# motherboard.net
KiCad netlist of a schematic drawn in EAGLE
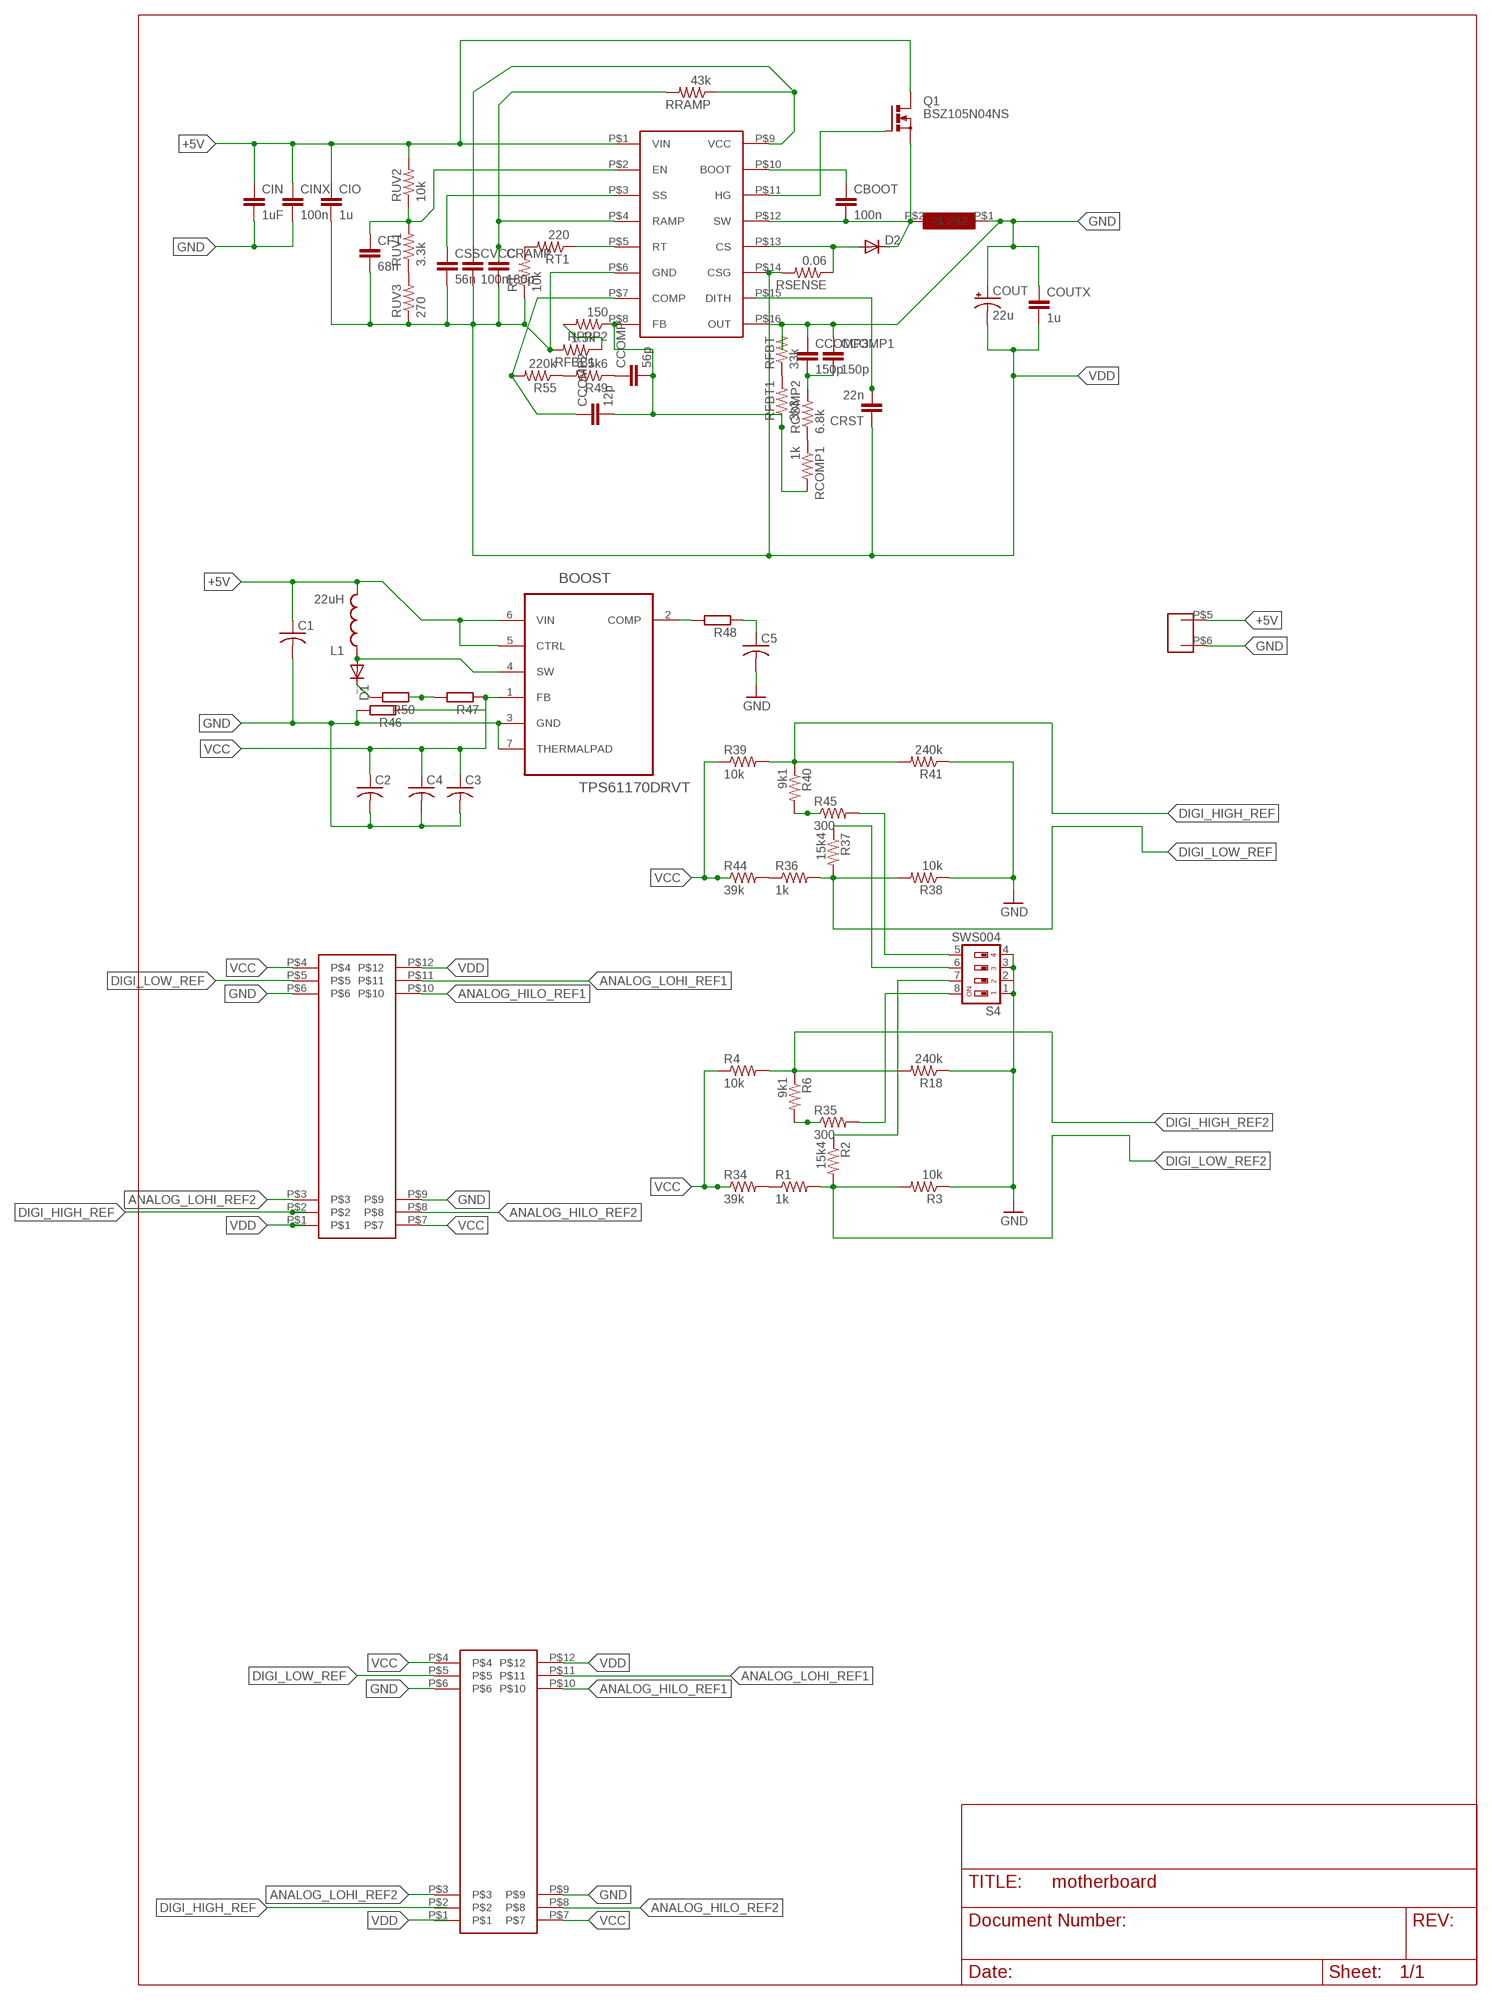
[diagram p0: schematic, sheet 1]

(export (version "E")
  (design (tool "Eeschema 10.0.6"))
  (components
    (comp (ref "BOOST")
      (value "TPS61170DRVT")
      (footprint "eagle-import:SON65P210X210X80-7N")
      (libsource (lib "eagle-import") (part "TPS61170DRVT"))
    )
    (comp (ref "C1")
      (value "C-USC1206")
      (footprint "eagle-import:C1206")
      (libsource (lib "eagle-import") (part "C-USC1206"))
    )
    (comp (ref "C2")
      (value "C-USC0805")
      (footprint "eagle-import:C0805")
      (libsource (lib "eagle-import") (part "C-USC0805"))
    )
    (comp (ref "C3")
      (value "C-USC1206")
      (footprint "eagle-import:C1206")
      (libsource (lib "eagle-import") (part "C-USC1206"))
    )
    (comp (ref "C4")
      (value "C-USC1206")
      (footprint "eagle-import:C1206")
      (libsource (lib "eagle-import") (part "C-USC1206"))
    )
    (comp (ref "C5")
      (value "C-USC1206")
      (footprint "eagle-import:C1206")
      (libsource (lib "eagle-import") (part "C-USC1206"))
    )
    (comp (ref "CBOOT")
      (value "100n")
      (footprint "eagle-import:C0805")
      (libsource (lib "eagle-import") (part "C-EUC0805"))
    )
    (comp (ref "CCOMP")
      (value "56p")
      (footprint "eagle-import:C0805")
      (libsource (lib "eagle-import") (part "C-EUC0805"))
    )
    (comp (ref "CCOMP1")
      (value "150p")
      (footprint "eagle-import:C0805")
      (libsource (lib "eagle-import") (part "C-EUC0805"))
    )
    (comp (ref "CCOMP2")
      (value "12p")
      (footprint "eagle-import:C0805")
      (libsource (lib "eagle-import") (part "C-EUC0805"))
    )
    (comp (ref "CCOMP3")
      (value "150p")
      (footprint "eagle-import:C0805")
      (libsource (lib "eagle-import") (part "C-EUC0805"))
    )
    (comp (ref "CFT")
      (value "68n")
      (footprint "eagle-import:C0805")
      (libsource (lib "eagle-import") (part "C-EUC0805"))
    )
    (comp (ref "CIN")
      (value "1uF")
      (footprint "eagle-import:C0805")
      (libsource (lib "eagle-import") (part "C-EUC0805"))
    )
    (comp (ref "CINX")
      (value "100n")
      (footprint "eagle-import:C0805")
      (libsource (lib "eagle-import") (part "C-EUC0805"))
    )
    (comp (ref "CIO")
      (value "1u")
      (footprint "eagle-import:C0805")
      (libsource (lib "eagle-import") (part "C-EUC0805"))
    )
    (comp (ref "COUT")
      (value "22u")
      (footprint "eagle-import:E5-5")
      (libsource (lib "eagle-import") (part "CPOL-USE5-5"))
    )
    (comp (ref "COUTX")
      (value "1u")
      (footprint "eagle-import:C0805")
      (libsource (lib "eagle-import") (part "C-EUC0805"))
    )
    (comp (ref "CRAMP")
      (value "180p")
      (footprint "eagle-import:C0805")
      (libsource (lib "eagle-import") (part "C-EUC0805"))
    )
    (comp (ref "CRST")
      (value "22n")
      (footprint "eagle-import:C0805")
      (libsource (lib "eagle-import") (part "C-EUC0805"))
    )
    (comp (ref "CSS")
      (value "56n")
      (footprint "eagle-import:C0805")
      (libsource (lib "eagle-import") (part "C-EUC0805"))
    )
    (comp (ref "CVCC")
      (value "100n")
      (footprint "eagle-import:C0805")
      (libsource (lib "eagle-import") (part "C-EUC0805"))
    )
    (comp (ref "D1")
      (value "DIODE-SOD123")
      (footprint "eagle-import:SOD123")
      (libsource (lib "eagle-import") (part "DIODE-SOD123"))
    )
    (comp (ref "D2")
      (value "DIODE-SOD123")
      (footprint "eagle-import:SOD123")
      (libsource (lib "eagle-import") (part "DIODE-SOD123"))
    )
    (comp (ref "L1")
      (value "22uH")
      (footprint "eagle-import:SRN6045")
      (libsource (lib "eagle-import") (part "INDUCTORBOURNS_SRN6045"))
    )
    (comp (ref "Q1")
      (value "BSZ105N04NS")
      (footprint "eagle-import:PG-TDSON-8")
      (libsource (lib "eagle-import") (part "BSZ105N04NS"))
    )
    (comp (ref "R1")
      (value "1k")
      (footprint "eagle-import:R0805")
      (libsource (lib "eagle-import") (part "R-US_R0805"))
    )
    (comp (ref "R2")
      (value "15k4")
      (footprint "eagle-import:R0805")
      (libsource (lib "eagle-import") (part "R-US_R0805"))
    )
    (comp (ref "R3")
      (value "10k")
      (footprint "eagle-import:R0805")
      (libsource (lib "eagle-import") (part "R-US_R0805"))
    )
    (comp (ref "R4")
      (value "10k")
      (footprint "eagle-import:R0805")
      (libsource (lib "eagle-import") (part "R-US_R0805"))
    )
    (comp (ref "R6")
      (value "9k1")
      (footprint "eagle-import:R0805")
      (libsource (lib "eagle-import") (part "R-US_R0805"))
    )
    (comp (ref "R18")
      (value "240k")
      (footprint "eagle-import:R0805")
      (libsource (lib "eagle-import") (part "R-US_R0805"))
    )
    (comp (ref "R34")
      (value "39k")
      (footprint "eagle-import:R0805")
      (libsource (lib "eagle-import") (part "R-US_R0805"))
    )
    (comp (ref "R35")
      (value "300")
      (footprint "eagle-import:R0805")
      (libsource (lib "eagle-import") (part "R-US_R0805"))
    )
    (comp (ref "R36")
      (value "1k")
      (footprint "eagle-import:R0805")
      (libsource (lib "eagle-import") (part "R-US_R0805"))
    )
    (comp (ref "R37")
      (value "15k4")
      (footprint "eagle-import:R0805")
      (libsource (lib "eagle-import") (part "R-US_R0805"))
    )
    (comp (ref "R38")
      (value "10k")
      (footprint "eagle-import:R0805")
      (libsource (lib "eagle-import") (part "R-US_R0805"))
    )
    (comp (ref "R39")
      (value "10k")
      (footprint "eagle-import:R0805")
      (libsource (lib "eagle-import") (part "R-US_R0805"))
    )
    (comp (ref "R40")
      (value "9k1")
      (footprint "eagle-import:R0805")
      (libsource (lib "eagle-import") (part "R-US_R0805"))
    )
    (comp (ref "R41")
      (value "240k")
      (footprint "eagle-import:R0805")
      (libsource (lib "eagle-import") (part "R-US_R0805"))
    )
    (comp (ref "R44")
      (value "39k")
      (footprint "eagle-import:R0805")
      (libsource (lib "eagle-import") (part "R-US_R0805"))
    )
    (comp (ref "R45")
      (value "300")
      (footprint "eagle-import:R0805")
      (libsource (lib "eagle-import") (part "R-US_R0805"))
    )
    (comp (ref "R46")
      (value "R-EU_R0805")
      (footprint "eagle-import:R0805")
      (libsource (lib "eagle-import") (part "R-EU_R0805"))
    )
    (comp (ref "R47")
      (value "R-EU_R0805")
      (footprint "eagle-import:R0805")
      (libsource (lib "eagle-import") (part "R-EU_R0805"))
    )
    (comp (ref "R48")
      (value "R-EU_R0805")
      (footprint "eagle-import:R0805")
      (libsource (lib "eagle-import") (part "R-EU_R0805"))
    )
    (comp (ref "R49")
      (value "5k6")
      (footprint "eagle-import:R0805")
      (libsource (lib "eagle-import") (part "R-US_R0805"))
    )
    (comp (ref "R50")
      (value "R-EU_R0805")
      (footprint "eagle-import:R0805")
      (libsource (lib "eagle-import") (part "R-EU_R0805"))
    )
    (comp (ref "R55")
      (value "220k")
      (footprint "eagle-import:R0805")
      (libsource (lib "eagle-import") (part "R-US_R0805"))
    )
    (comp (ref "RCOMP1")
      (value "1k")
      (footprint "eagle-import:R0805")
      (libsource (lib "eagle-import") (part "R-US_R0805"))
    )
    (comp (ref "RCOMP2")
      (value "6.8k")
      (footprint "eagle-import:R0805")
      (libsource (lib "eagle-import") (part "R-US_R0805"))
    )
    (comp (ref "RFBB1")
      (value "1.5k")
      (footprint "eagle-import:R0805")
      (libsource (lib "eagle-import") (part "R-US_R0805"))
    )
    (comp (ref "RFBT")
      (value "33k")
      (footprint "eagle-import:R0805")
      (libsource (lib "eagle-import") (part "R-US_R0805"))
    )
    (comp (ref "RFBT1")
      (value "3k3")
      (footprint "eagle-import:R0805")
      (libsource (lib "eagle-import") (part "R-US_R0805"))
    )
    (comp (ref "RFPP2")
      (value "150")
      (footprint "eagle-import:R0805")
      (libsource (lib "eagle-import") (part "R-US_R0805"))
    )
    (comp (ref "RRAMP")
      (value "43k")
      (footprint "eagle-import:R0805")
      (libsource (lib "eagle-import") (part "R-US_R0805"))
    )
    (comp (ref "RSENSE")
      (value "0.06")
      (footprint "eagle-import:R0805")
      (libsource (lib "eagle-import") (part "R-US_R0805"))
    )
    (comp (ref "RT")
      (value "10k")
      (footprint "eagle-import:R0805")
      (libsource (lib "eagle-import") (part "R-US_R0805"))
    )
    (comp (ref "RT1")
      (value "220")
      (footprint "eagle-import:R0805")
      (libsource (lib "eagle-import") (part "R-US_R0805"))
    )
    (comp (ref "RUV1")
      (value "3.3k")
      (footprint "eagle-import:R0805")
      (libsource (lib "eagle-import") (part "R-US_R0805"))
    )
    (comp (ref "RUV2")
      (value "10k")
      (footprint "eagle-import:R0805")
      (libsource (lib "eagle-import") (part "R-US_R0805"))
    )
    (comp (ref "RUV3")
      (value "270")
      (footprint "eagle-import:R0805")
      (libsource (lib "eagle-import") (part "R-US_R0805"))
    )
    (comp (ref "S4")
      (value "SWS004")
      (footprint "eagle-import:SMS-004")
      (libsource (lib "eagle-import") (part "SWS004"))
    )
    (comp (ref "U$1")
      (value "MODULE_CONNECTOR")
      (footprint "eagle-import:MODULE_CONNECTOR")
      (libsource (lib "eagle-import") (part "MODULE_CONNECTOR"))
    )
    (comp (ref "U$2")
      (value "LM5088")
      (footprint "eagle-import:LM5088")
      (libsource (lib "eagle-import") (part "LM5088"))
    )
    (comp (ref "U$3")
      (value "KLICK_INDUCTOR01")
      (footprint "eagle-import:KLICK_INDUCTOR01")
      (libsource (lib "eagle-import") (part "KLICK_INDUCTOR01"))
    )
    (comp (ref "U$4")
      (value "5.08PITCHTERMINAL")
      (footprint "eagle-import:10KPL508")
      (libsource (lib "eagle-import") (part "5.08PITCHTERMINAL"))
    )
    (comp (ref "U$5")
      (value "MODULE_CONNECTOR")
      (footprint "eagle-import:MODULE_CONNECTOR")
      (libsource (lib "eagle-import") (part "MODULE_CONNECTOR"))
    )
  )
  (nets
    (net (code "1") (name "+5V") (class "Default")
      (node (ref "BOOST") (pin "5") (pinfunction "CTRL_5") (pintype "input"))
      (node (ref "BOOST") (pin "6") (pinfunction "VIN_6") (pintype "power_in"))
      (node (ref "C1") (pin "1") (pinfunction "1_1") (pintype "passive"))
      (node (ref "CIN") (pin "1") (pinfunction "1_1") (pintype "passive"))
      (node (ref "CINX") (pin "1") (pinfunction "1_1") (pintype "passive"))
      (node (ref "CIO") (pin "1") (pinfunction "1_1") (pintype "passive"))
      (node (ref "L1") (pin "2") (pinfunction "2_2") (pintype "passive"))
      (node (ref "Q1") (pin "5") (pinfunction "D_5") (pintype "passive"))
      (node (ref "Q1") (pin "6") (pinfunction "D_6") (pintype "passive"))
      (node (ref "Q1") (pin "7") (pinfunction "D_7") (pintype "passive"))
      (node (ref "Q1") (pin "8") (pinfunction "D_8") (pintype "passive"))
      (node (ref "Q1") (pin "TH") (pinfunction "D_TH") (pintype "passive"))
      (node (ref "RUV2") (pin "2") (pinfunction "2_2") (pintype "passive"))
      (node (ref "U$2") (pin "P$1") (pinfunction "VIN_P$1") (pintype "bidirectional"))
      (node (ref "U$4") (pin "P$5") (pinfunction "P$5_P$5") (pintype "bidirectional"))
    )
    (net (code "2") (name "ANALOG_HILO_REF1") (class "Default")
      (node (ref "U$1") (pin "P$10") (pinfunction "P$10_P$10") (pintype "bidirectional"))
      (node (ref "U$5") (pin "P$10") (pinfunction "P$10_P$10") (pintype "bidirectional"))
    )
    (net (code "3") (name "ANALOG_HILO_REF2") (class "Default")
      (node (ref "U$1") (pin "P$8") (pinfunction "P$8_P$8") (pintype "bidirectional"))
      (node (ref "U$5") (pin "P$8") (pinfunction "P$8_P$8") (pintype "bidirectional"))
    )
    (net (code "4") (name "ANALOG_LOHI_REF1") (class "Default")
      (node (ref "U$1") (pin "P$11") (pinfunction "P$11_P$11") (pintype "bidirectional"))
      (node (ref "U$5") (pin "P$11") (pinfunction "P$11_P$11") (pintype "bidirectional"))
    )
    (net (code "5") (name "ANALOG_LOHI_REF2") (class "Default")
      (node (ref "U$1") (pin "P$3") (pinfunction "P$3_P$3") (pintype "bidirectional"))
      (node (ref "U$5") (pin "P$3") (pinfunction "P$3_P$3") (pintype "bidirectional"))
    )
    (net (code "6") (name "DIGI_HIGH_REF") (class "Default")
      (node (ref "R39") (pin "2") (pinfunction "2_2") (pintype "passive"))
      (node (ref "R40") (pin "1") (pinfunction "1_1") (pintype "passive"))
      (node (ref "R41") (pin "2") (pinfunction "2_2") (pintype "passive"))
      (node (ref "U$1") (pin "P$2") (pinfunction "P$2_P$2") (pintype "bidirectional"))
    )
    (net (code "7") (name "DIGI_HIGH_REF2") (class "Default")
      (node (ref "R18") (pin "2") (pinfunction "2_2") (pintype "passive"))
      (node (ref "R4") (pin "2") (pinfunction "2_2") (pintype "passive"))
      (node (ref "R6") (pin "1") (pinfunction "1_1") (pintype "passive"))
    )
    (net (code "8") (name "DIGI_LOW_REF") (class "Default")
      (node (ref "R36") (pin "2") (pinfunction "2_2") (pintype "passive"))
      (node (ref "R37") (pin "2") (pinfunction "2_2") (pintype "passive"))
      (node (ref "R38") (pin "2") (pinfunction "2_2") (pintype "passive"))
      (node (ref "U$1") (pin "P$5") (pinfunction "P$5_P$5") (pintype "bidirectional"))
      (node (ref "U$5") (pin "P$5") (pinfunction "P$5_P$5") (pintype "bidirectional"))
    )
    (net (code "9") (name "DIGI_LOW_REF2") (class "Default")
      (node (ref "R1") (pin "2") (pinfunction "2_2") (pintype "passive"))
      (node (ref "R2") (pin "2") (pinfunction "2_2") (pintype "passive"))
      (node (ref "R3") (pin "2") (pinfunction "2_2") (pintype "passive"))
    )
    (net (code "10") (name "GND") (class "Default")
      (node (ref "BOOST") (pin "3") (pinfunction "GND_3") (pintype "passive"))
      (node (ref "BOOST") (pin "7") (pinfunction "THERMALPAD_7") (pintype "passive"))
      (node (ref "C1") (pin "2") (pinfunction "2_2") (pintype "passive"))
      (node (ref "C2") (pin "2") (pinfunction "2_2") (pintype "passive"))
      (node (ref "C3") (pin "2") (pinfunction "2_2") (pintype "passive"))
      (node (ref "C4") (pin "2") (pinfunction "2_2") (pintype "passive"))
      (node (ref "C5") (pin "2") (pinfunction "2_2") (pintype "passive"))
      (node (ref "CCOMP1") (pin "1") (pinfunction "1_1") (pintype "passive"))
      (node (ref "CCOMP3") (pin "1") (pinfunction "1_1") (pintype "passive"))
      (node (ref "CIN") (pin "2") (pinfunction "2_2") (pintype "passive"))
      (node (ref "CINX") (pin "2") (pinfunction "2_2") (pintype "passive"))
      (node (ref "COUT") (pin "+") (pinfunction "+_+") (pintype "passive"))
      (node (ref "COUTX") (pin "1") (pinfunction "1_1") (pintype "passive"))
      (node (ref "R18") (pin "1") (pinfunction "1_1") (pintype "passive"))
      (node (ref "R3") (pin "1") (pinfunction "1_1") (pintype "passive"))
      (node (ref "R38") (pin "1") (pinfunction "1_1") (pintype "passive"))
      (node (ref "R41") (pin "1") (pinfunction "1_1") (pintype "passive"))
      (node (ref "R46") (pin "2") (pinfunction "2_2") (pintype "passive"))
      (node (ref "RFBT") (pin "2") (pinfunction "2_2") (pintype "passive"))
      (node (ref "S4") (pin "1") (pinfunction "1_1") (pintype "passive"))
      (node (ref "S4") (pin "2") (pinfunction "2_2") (pintype "passive"))
      (node (ref "S4") (pin "3") (pinfunction "3_3") (pintype "passive"))
      (node (ref "S4") (pin "4") (pinfunction "4_4") (pintype "passive"))
      (node (ref "U$1") (pin "P$6") (pinfunction "P$6_P$6") (pintype "bidirectional"))
      (node (ref "U$1") (pin "P$9") (pinfunction "P$9_P$9") (pintype "bidirectional"))
      (node (ref "U$2") (pin "P$16") (pinfunction "OUT_P$16") (pintype "bidirectional"))
      (node (ref "U$3") (pin "P$1") (pinfunction "P$1_P$1") (pintype "bidirectional"))
      (node (ref "U$4") (pin "P$6") (pinfunction "P$6_P$6") (pintype "bidirectional"))
      (node (ref "U$5") (pin "P$6") (pinfunction "P$6_P$6") (pintype "bidirectional"))
      (node (ref "U$5") (pin "P$9") (pinfunction "P$9_P$9") (pintype "bidirectional"))
    )
    (net (code "11") (name "Net-(BOOST-COMP)") (class "Default")
      (node (ref "BOOST") (pin "2") (pinfunction "COMP_2") (pintype "output"))
      (node (ref "R48") (pin "2") (pinfunction "2_2") (pintype "passive"))
    )
    (net (code "12") (name "Net-(BOOST-SW)") (class "Default")
      (node (ref "BOOST") (pin "4") (pinfunction "SW_4") (pintype "input"))
      (node (ref "D1") (pin "A") (pinfunction "A_A") (pintype "passive"))
      (node (ref "L1") (pin "1") (pinfunction "1_1") (pintype "passive"))
    )
    (net (code "13") (name "Net-(C5-Pad1)") (class "Default")
      (node (ref "C5") (pin "1") (pinfunction "1_1") (pintype "passive"))
      (node (ref "R48") (pin "1") (pinfunction "1_1") (pintype "passive"))
    )
    (net (code "14") (name "Net-(CCOMP-Pad1)") (class "Default")
      (node (ref "CCOMP") (pin "1") (pinfunction "1_1") (pintype "passive"))
      (node (ref "R49") (pin "1") (pinfunction "1_1") (pintype "passive"))
    )
    (net (code "15") (name "Net-(CCOMP1-Pad2)") (class "Default")
      (node (ref "CCOMP1") (pin "2") (pinfunction "2_2") (pintype "passive"))
      (node (ref "CCOMP3") (pin "2") (pinfunction "2_2") (pintype "passive"))
      (node (ref "RCOMP2") (pin "2") (pinfunction "2_2") (pintype "passive"))
    )
    (net (code "16") (name "Net-(D1-PadC)") (class "Default")
      (node (ref "D1") (pin "C") (pinfunction "C_C") (pintype "passive"))
      (node (ref "R50") (pin "2") (pinfunction "2_2") (pintype "passive"))
    )
    (net (code "17") (name "Net-(Q1-G)") (class "Default")
      (node (ref "Q1") (pin "4") (pinfunction "G_4") (pintype "passive"))
      (node (ref "U$2") (pin "P$11") (pinfunction "HG_P$11") (pintype "bidirectional"))
    )
    (net (code "18") (name "Net-(R1-Pad1)") (class "Default")
      (node (ref "R1") (pin "1") (pinfunction "1_1") (pintype "passive"))
      (node (ref "R34") (pin "2") (pinfunction "2_2") (pintype "passive"))
    )
    (net (code "19") (name "Net-(R2-Pad1)") (class "Default")
      (node (ref "R2") (pin "1") (pinfunction "1_1") (pintype "passive"))
      (node (ref "S4") (pin "7") (pinfunction "7_7") (pintype "passive"))
    )
    (net (code "20") (name "Net-(R35-Pad1)") (class "Default")
      (node (ref "R35") (pin "1") (pinfunction "1_1") (pintype "passive"))
      (node (ref "R6") (pin "2") (pinfunction "2_2") (pintype "passive"))
    )
    (net (code "21") (name "Net-(R35-Pad2)") (class "Default")
      (node (ref "R35") (pin "2") (pinfunction "2_2") (pintype "passive"))
      (node (ref "S4") (pin "8") (pinfunction "8_8") (pintype "passive"))
    )
    (net (code "22") (name "Net-(R36-Pad1)") (class "Default")
      (node (ref "R36") (pin "1") (pinfunction "1_1") (pintype "passive"))
      (node (ref "R44") (pin "2") (pinfunction "2_2") (pintype "passive"))
    )
    (net (code "23") (name "Net-(R37-Pad1)") (class "Default")
      (node (ref "R37") (pin "1") (pinfunction "1_1") (pintype "passive"))
      (node (ref "S4") (pin "6") (pinfunction "6_6") (pintype "passive"))
    )
    (net (code "24") (name "Net-(R40-Pad2)") (class "Default")
      (node (ref "R40") (pin "2") (pinfunction "2_2") (pintype "passive"))
      (node (ref "R45") (pin "1") (pinfunction "1_1") (pintype "passive"))
    )
    (net (code "25") (name "Net-(R45-Pad2)") (class "Default")
      (node (ref "R45") (pin "2") (pinfunction "2_2") (pintype "passive"))
      (node (ref "S4") (pin "5") (pinfunction "5_5") (pintype "passive"))
    )
    (net (code "26") (name "Net-(R47-Pad2)") (class "Default")
      (node (ref "R47") (pin "2") (pinfunction "2_2") (pintype "passive"))
      (node (ref "R50") (pin "1") (pinfunction "1_1") (pintype "passive"))
    )
    (net (code "27") (name "Net-(R49-Pad2)") (class "Default")
      (node (ref "R49") (pin "2") (pinfunction "2_2") (pintype "passive"))
      (node (ref "R55") (pin "1") (pinfunction "1_1") (pintype "passive"))
    )
    (net (code "28") (name "Net-(RCOMP1-Pad1)") (class "Default")
      (node (ref "RCOMP1") (pin "1") (pinfunction "1_1") (pintype "passive"))
      (node (ref "RCOMP2") (pin "1") (pinfunction "1_1") (pintype "passive"))
    )
    (net (code "29") (name "Net-(RFBB1-Pad1)") (class "Default")
      (node (ref "RFBB1") (pin "1") (pinfunction "1_1") (pintype "passive"))
      (node (ref "RFPP2") (pin "2") (pinfunction "2_2") (pintype "passive"))
    )
    (net (code "30") (name "Net-(RFBT-Pad1)") (class "Default")
      (node (ref "RFBT") (pin "1") (pinfunction "1_1") (pintype "passive"))
      (node (ref "RFBT1") (pin "2") (pinfunction "2_2") (pintype "passive"))
    )
    (net (code "31") (name "Net-(RT-Pad2)") (class "Default")
      (node (ref "RT") (pin "2") (pinfunction "2_2") (pintype "passive"))
      (node (ref "RT1") (pin "2") (pinfunction "2_2") (pintype "passive"))
    )
    (net (code "32") (name "Net-(RUV1-Pad1)") (class "Default")
      (node (ref "RUV1") (pin "1") (pinfunction "1_1") (pintype "passive"))
      (node (ref "RUV3") (pin "2") (pinfunction "2_2") (pintype "passive"))
    )
    (net (code "33") (name "Net-(U$2-BOOT)") (class "Default")
      (node (ref "CBOOT") (pin "1") (pinfunction "1_1") (pintype "passive"))
      (node (ref "U$2") (pin "P$10") (pinfunction "BOOT_P$10") (pintype "bidirectional"))
    )
    (net (code "34") (name "Net-(U$2-COMP)") (class "Default")
      (node (ref "CCOMP2") (pin "1") (pinfunction "1_1") (pintype "passive"))
      (node (ref "R55") (pin "2") (pinfunction "2_2") (pintype "passive"))
      (node (ref "U$2") (pin "P$7") (pinfunction "COMP_P$7") (pintype "bidirectional"))
    )
    (net (code "35") (name "Net-(U$2-CS)") (class "Default")
      (node (ref "D2") (pin "A") (pinfunction "A_A") (pintype "passive"))
      (node (ref "RSENSE") (pin "1") (pinfunction "1_1") (pintype "passive"))
      (node (ref "U$2") (pin "P$13") (pinfunction "CS_P$13") (pintype "bidirectional"))
    )
    (net (code "36") (name "Net-(U$2-DITH)") (class "Default")
      (node (ref "CRST") (pin "2") (pinfunction "2_2") (pintype "passive"))
      (node (ref "U$2") (pin "P$15") (pinfunction "DITH_P$15") (pintype "bidirectional"))
    )
    (net (code "37") (name "Net-(U$2-EN)") (class "Default")
      (node (ref "CFT") (pin "1") (pinfunction "1_1") (pintype "passive"))
      (node (ref "RUV1") (pin "2") (pinfunction "2_2") (pintype "passive"))
      (node (ref "RUV2") (pin "1") (pinfunction "1_1") (pintype "passive"))
      (node (ref "U$2") (pin "P$2") (pinfunction "EN_P$2") (pintype "bidirectional"))
    )
    (net (code "38") (name "Net-(U$2-FB)") (class "Default")
      (node (ref "CCOMP") (pin "2") (pinfunction "2_2") (pintype "passive"))
      (node (ref "CCOMP2") (pin "2") (pinfunction "2_2") (pintype "passive"))
      (node (ref "RCOMP1") (pin "2") (pinfunction "2_2") (pintype "passive"))
      (node (ref "RFBT1") (pin "1") (pinfunction "1_1") (pintype "passive"))
      (node (ref "RFPP2") (pin "1") (pinfunction "1_1") (pintype "passive"))
      (node (ref "U$2") (pin "P$8") (pinfunction "FB_P$8") (pintype "bidirectional"))
    )
    (net (code "39") (name "Net-(U$2-RAMP)") (class "Default")
      (node (ref "CRAMP") (pin "1") (pinfunction "1_1") (pintype "passive"))
      (node (ref "RRAMP") (pin "2") (pinfunction "2_2") (pintype "passive"))
      (node (ref "U$2") (pin "P$4") (pinfunction "RAMP_P$4") (pintype "bidirectional"))
    )
    (net (code "40") (name "Net-(U$2-RT)") (class "Default")
      (node (ref "RT1") (pin "1") (pinfunction "1_1") (pintype "passive"))
      (node (ref "U$2") (pin "P$5") (pinfunction "RT_P$5") (pintype "bidirectional"))
    )
    (net (code "41") (name "Net-(U$2-SS)") (class "Default")
      (node (ref "CSS") (pin "1") (pinfunction "1_1") (pintype "passive"))
      (node (ref "U$2") (pin "P$3") (pinfunction "SS_P$3") (pintype "bidirectional"))
    )
    (net (code "42") (name "Net-(U$2-SW)") (class "Default")
      (node (ref "CBOOT") (pin "2") (pinfunction "2_2") (pintype "passive"))
      (node (ref "D2") (pin "C") (pinfunction "C_C") (pintype "passive"))
      (node (ref "Q1") (pin "1") (pinfunction "S_1") (pintype "passive"))
      (node (ref "Q1") (pin "2") (pinfunction "S_2") (pintype "passive"))
      (node (ref "Q1") (pin "3") (pinfunction "S_3") (pintype "passive"))
      (node (ref "U$2") (pin "P$12") (pinfunction "SW_P$12") (pintype "bidirectional"))
      (node (ref "U$3") (pin "P$2") (pinfunction "P$2_P$2") (pintype "bidirectional"))
    )
    (net (code "43") (name "Net-(U$2-VCC)") (class "Default")
      (node (ref "CVCC") (pin "1") (pinfunction "1_1") (pintype "passive"))
      (node (ref "RRAMP") (pin "1") (pinfunction "1_1") (pintype "passive"))
      (node (ref "U$2") (pin "P$9") (pinfunction "VCC_P$9") (pintype "bidirectional"))
    )
    (net (code "44") (name "VCC") (class "Default")
      (node (ref "BOOST") (pin "1") (pinfunction "FB_1") (pintype "input"))
      (node (ref "C2") (pin "1") (pinfunction "1_1") (pintype "passive"))
      (node (ref "C3") (pin "1") (pinfunction "1_1") (pintype "passive"))
      (node (ref "C4") (pin "1") (pinfunction "1_1") (pintype "passive"))
      (node (ref "R34") (pin "1") (pinfunction "1_1") (pintype "passive"))
      (node (ref "R39") (pin "1") (pinfunction "1_1") (pintype "passive"))
      (node (ref "R4") (pin "1") (pinfunction "1_1") (pintype "passive"))
      (node (ref "R44") (pin "1") (pinfunction "1_1") (pintype "passive"))
      (node (ref "R46") (pin "1") (pinfunction "1_1") (pintype "passive"))
      (node (ref "R47") (pin "1") (pinfunction "1_1") (pintype "passive"))
      (node (ref "U$1") (pin "P$4") (pinfunction "P$4_P$4") (pintype "bidirectional"))
      (node (ref "U$1") (pin "P$7") (pinfunction "P$7_P$7") (pintype "bidirectional"))
      (node (ref "U$5") (pin "P$4") (pinfunction "P$4_P$4") (pintype "bidirectional"))
      (node (ref "U$5") (pin "P$7") (pinfunction "P$7_P$7") (pintype "bidirectional"))
    )
    (net (code "45") (name "VDD") (class "Default")
      (node (ref "CFT") (pin "2") (pinfunction "2_2") (pintype "passive"))
      (node (ref "CIO") (pin "2") (pinfunction "2_2") (pintype "passive"))
      (node (ref "COUT") (pin "-") (pinfunction "-_-") (pintype "passive"))
      (node (ref "COUTX") (pin "2") (pinfunction "2_2") (pintype "passive"))
      (node (ref "CRAMP") (pin "2") (pinfunction "2_2") (pintype "passive"))
      (node (ref "CRST") (pin "1") (pinfunction "1_1") (pintype "passive"))
      (node (ref "CSS") (pin "2") (pinfunction "2_2") (pintype "passive"))
      (node (ref "CVCC") (pin "2") (pinfunction "2_2") (pintype "passive"))
      (node (ref "RFBB1") (pin "2") (pinfunction "2_2") (pintype "passive"))
      (node (ref "RSENSE") (pin "2") (pinfunction "2_2") (pintype "passive"))
      (node (ref "RT") (pin "1") (pinfunction "1_1") (pintype "passive"))
      (node (ref "RUV3") (pin "1") (pinfunction "1_1") (pintype "passive"))
      (node (ref "U$1") (pin "P$1") (pinfunction "P$1_P$1") (pintype "bidirectional"))
      (node (ref "U$1") (pin "P$12") (pinfunction "P$12_P$12") (pintype "bidirectional"))
      (node (ref "U$2") (pin "P$14") (pinfunction "CSG_P$14") (pintype "bidirectional"))
      (node (ref "U$2") (pin "P$6") (pinfunction "GND_P$6") (pintype "bidirectional"))
      (node (ref "U$5") (pin "P$12") (pinfunction "P$12_P$12") (pintype "bidirectional"))
    )
    (net (code "46") (name "unconnected-(U$5-PadP$1)") (class "Default")
      (node (ref "U$5") (pin "P$1") (pinfunction "P$1_P$1") (pintype "bidirectional"))
    )
    (net (code "47") (name "unconnected-(U$5-PadP$2)") (class "Default")
      (node (ref "U$5") (pin "P$2") (pinfunction "P$2_P$2") (pintype "bidirectional"))
    )
  )
)
